# TR_i3_6A_Module_v5.net
KiCad netlist of a schematic drawn in EAGLE
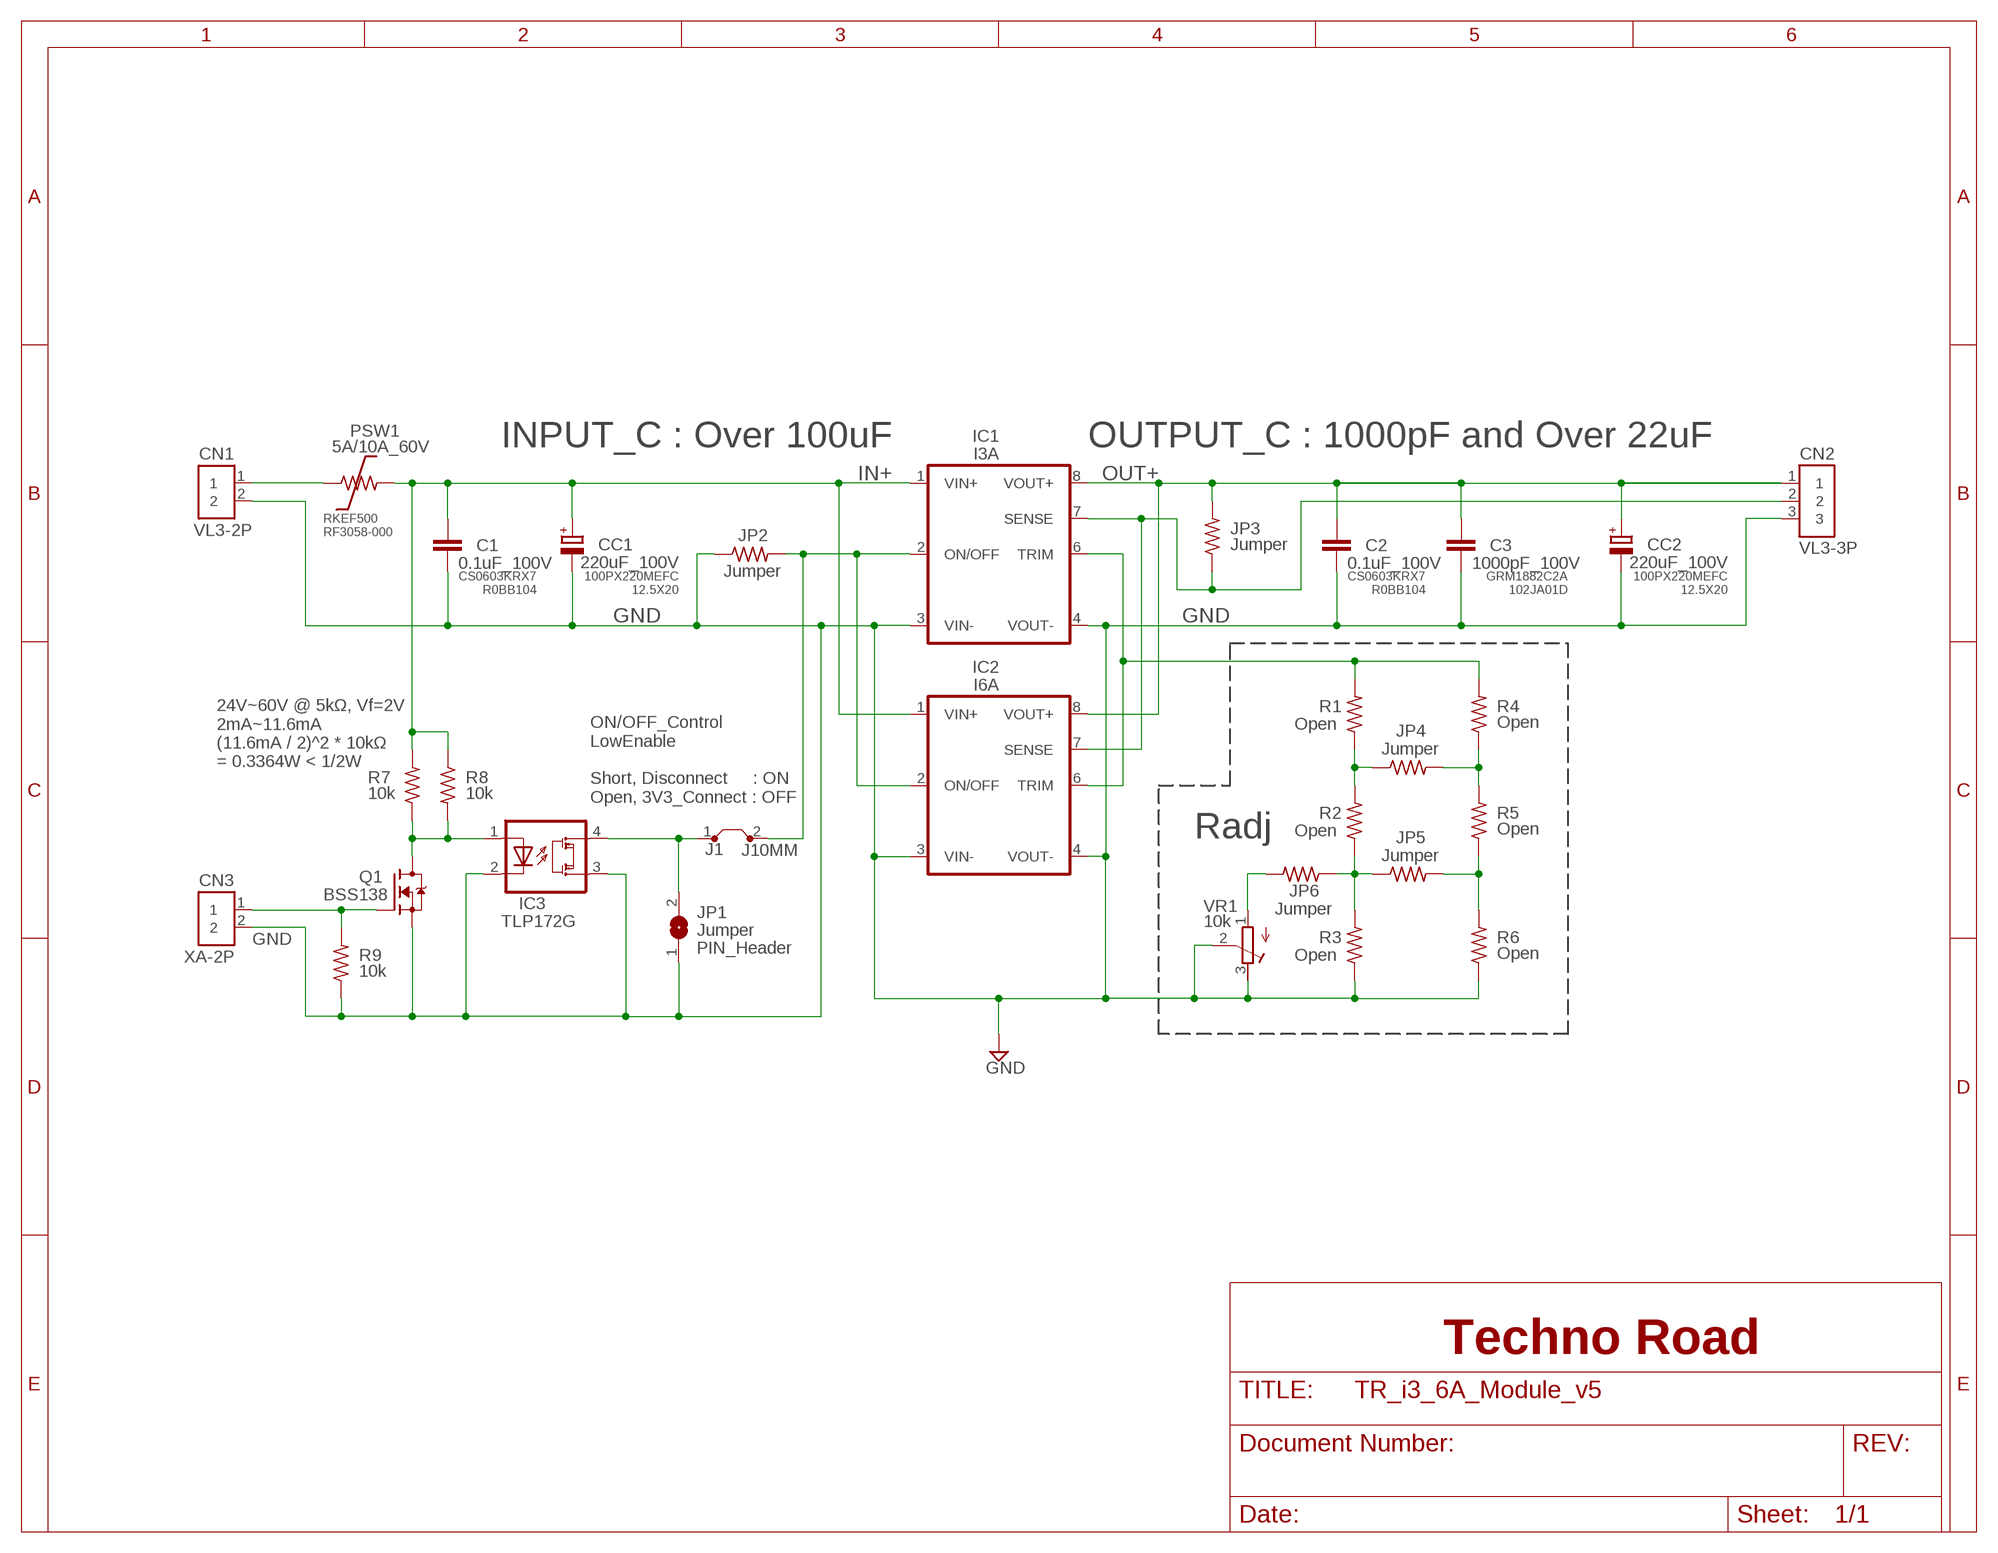
[diagram p0: schematic, sheet 1]

(export (version "E")
  (design (tool "Eeschema 10.0.6"))
  (components
    (comp (ref "C1")
      (value "0.1uF_100V")
      (footprint "eagle-import:C1608")
      (libsource (lib "eagle-import") (part "C1608"))
    )
    (comp (ref "C2")
      (value "0.1uF_100V")
      (footprint "eagle-import:C1608")
      (libsource (lib "eagle-import") (part "C1608"))
    )
    (comp (ref "C3")
      (value "1000pF_100V")
      (footprint "eagle-import:C1608")
      (libsource (lib "eagle-import") (part "C1608"))
    )
    (comp (ref "CC1")
      (value "220uF_100V")
      (footprint "eagle-import:CC0510")
      (libsource (lib "eagle-import") (part "CC0510"))
    )
    (comp (ref "CC2")
      (value "220uF_100V")
      (footprint "eagle-import:CC0510")
      (libsource (lib "eagle-import") (part "CC0510"))
    )
    (comp (ref "CN1")
      (value "VL3-2P")
      (footprint "eagle-import:VL3-2P")
      (libsource (lib "eagle-import") (part "2PVL3"))
    )
    (comp (ref "CN2")
      (value "VL3-3P")
      (footprint "eagle-import:VL3-3P")
      (libsource (lib "eagle-import") (part "3PVL3"))
    )
    (comp (ref "CN3")
      (value "XA-2P")
      (footprint "eagle-import:XA-2P_NH")
      (libsource (lib "eagle-import") (part "2PXA_NH"))
    )
    (comp (ref "IC1")
      (value "I3A")
      (footprint "eagle-import:I3A_SERIES")
      (libsource (lib "eagle-import") (part "I3A/I6A_SEREISI3A"))
    )
    (comp (ref "IC2")
      (value "I6A")
      (footprint "eagle-import:I6A_SERIES")
      (libsource (lib "eagle-import") (part "I3A/I6A_SEREISI6A"))
    )
    (comp (ref "IC3")
      (value "TLP172G")
      (footprint "eagle-import:11-5H1")
      (libsource (lib "eagle-import") (part "TLP172"))
    )
    (comp (ref "J1")
      (value "J10MM")
      (footprint "eagle-import:10")
      (libsource (lib "eagle-import") (part "J10MM"))
    )
    (comp (ref "JP1")
      (value "Jumper")
      (footprint "eagle-import:JP1D_HOLE")
      (libsource (lib "eagle-import") (part "JP1D"))
    )
    (comp (ref "JP2")
      (value "Jumper")
      (footprint "eagle-import:R1608_LARGE_PAD")
      (libsource (lib "eagle-import") (part "R1608_LARGE_PAD"))
    )
    (comp (ref "JP3")
      (value "Jumper")
      (footprint "eagle-import:R1608_LARGE_PAD")
      (libsource (lib "eagle-import") (part "R1608_LARGE_PAD"))
    )
    (comp (ref "JP4")
      (value "Jumper")
      (footprint "eagle-import:R1608_LARGE_PAD")
      (libsource (lib "eagle-import") (part "R1608_LARGE_PAD"))
    )
    (comp (ref "JP5")
      (value "Jumper")
      (footprint "eagle-import:R1608_LARGE_PAD")
      (libsource (lib "eagle-import") (part "R1608_LARGE_PAD"))
    )
    (comp (ref "JP6")
      (value "Jumper")
      (footprint "eagle-import:R1608_LARGE_PAD")
      (libsource (lib "eagle-import") (part "R1608_LARGE_PAD"))
    )
    (comp (ref "PSW1")
      (value "5A/10A_60V")
      (footprint "eagle-import:PSW-10.16MM_4MM")
      (libsource (lib "eagle-import") (part "PSW10.16MM_4MM"))
    )
    (comp (ref "Q1")
      (value "BSS138")
      (footprint "eagle-import:SOT-23-3")
      (libsource (lib "eagle-import") (part "BSS138"))
    )
    (comp (ref "R1")
      (value "Open")
      (footprint "eagle-import:R1608_LARGE_PAD")
      (libsource (lib "eagle-import") (part "R1608_LARGE_PAD"))
    )
    (comp (ref "R2")
      (value "Open")
      (footprint "eagle-import:R1608_LARGE_PAD")
      (libsource (lib "eagle-import") (part "R1608_LARGE_PAD"))
    )
    (comp (ref "R3")
      (value "Open")
      (footprint "eagle-import:R1608_LARGE_PAD")
      (libsource (lib "eagle-import") (part "R1608_LARGE_PAD"))
    )
    (comp (ref "R4")
      (value "Open")
      (footprint "eagle-import:R1608_LARGE_PAD")
      (libsource (lib "eagle-import") (part "R1608_LARGE_PAD"))
    )
    (comp (ref "R5")
      (value "Open")
      (footprint "eagle-import:R1608_LARGE_PAD")
      (libsource (lib "eagle-import") (part "R1608_LARGE_PAD"))
    )
    (comp (ref "R6")
      (value "Open")
      (footprint "eagle-import:R1608_LARGE_PAD")
      (libsource (lib "eagle-import") (part "R1608_LARGE_PAD"))
    )
    (comp (ref "R7")
      (value "10k")
      (footprint "eagle-import:0204V")
      (libsource (lib "eagle-import") (part "R-US_0204/2V"))
    )
    (comp (ref "R8")
      (value "10k")
      (footprint "eagle-import:0204V")
      (libsource (lib "eagle-import") (part "R-US_0204/2V"))
    )
    (comp (ref "R9")
      (value "10k")
      (footprint "eagle-import:R1608_LARGE_PAD")
      (libsource (lib "eagle-import") (part "R1608_LARGE_PAD"))
    )
    (comp (ref "VR1")
      (value "10k")
      (footprint "eagle-import:3361P")
      (libsource (lib "eagle-import") (part "R-TRIM3361P"))
    )
  )
  (nets
    (net (code "1") (name "/IN+") (class "Default")
      (node (ref "C1") (pin "1") (pinfunction "1_1") (pintype "passive"))
      (node (ref "CC1") (pin "+") (pinfunction "+_+") (pintype "passive"))
      (node (ref "IC1") (pin "1") (pinfunction "VIN+_1") (pintype "passive"))
      (node (ref "IC2") (pin "1") (pinfunction "VIN+_1") (pintype "passive"))
      (node (ref "PSW1") (pin "2") (pinfunction "2_2") (pintype "passive"))
      (node (ref "R7") (pin "2") (pinfunction "2_2") (pintype "passive"))
      (node (ref "R8") (pin "1") (pinfunction "1_1") (pintype "passive"))
    )
    (net (code "2") (name "/OUT+") (class "Default")
      (node (ref "C2") (pin "1") (pinfunction "1_1") (pintype "passive"))
      (node (ref "C3") (pin "1") (pinfunction "1_1") (pintype "passive"))
      (node (ref "CC2") (pin "+") (pinfunction "+_+") (pintype "passive"))
      (node (ref "CN2") (pin "1") (pinfunction "1_1") (pintype "passive"))
      (node (ref "IC1") (pin "8") (pinfunction "VOUT+_8") (pintype "passive"))
      (node (ref "IC2") (pin "8") (pinfunction "VOUT+_8") (pintype "passive"))
      (node (ref "JP3") (pin "2") (pinfunction "2_2") (pintype "passive"))
    )
    (net (code "3") (name "GND") (class "Default")
      (node (ref "C1") (pin "2") (pinfunction "2_2") (pintype "passive"))
      (node (ref "C2") (pin "2") (pinfunction "2_2") (pintype "passive"))
      (node (ref "C3") (pin "2") (pinfunction "2_2") (pintype "passive"))
      (node (ref "CC1") (pin "-") (pinfunction "-_-") (pintype "passive"))
      (node (ref "CC2") (pin "-") (pinfunction "-_-") (pintype "passive"))
      (node (ref "CN1") (pin "2") (pinfunction "2_2") (pintype "passive"))
      (node (ref "CN2") (pin "3") (pinfunction "3_3") (pintype "passive"))
      (node (ref "CN3") (pin "2") (pinfunction "2_2") (pintype "passive"))
      (node (ref "IC1") (pin "3") (pinfunction "VIN-_3") (pintype "passive"))
      (node (ref "IC1") (pin "4") (pinfunction "VOUT-_4") (pintype "passive"))
      (node (ref "IC2") (pin "3") (pinfunction "VIN-_3") (pintype "passive"))
      (node (ref "IC2") (pin "4") (pinfunction "VOUT-_4") (pintype "passive"))
      (node (ref "IC3") (pin "2") (pinfunction "C1_2") (pintype "passive"))
      (node (ref "IC3") (pin "3") (pinfunction "DRN1_3") (pintype "passive"))
      (node (ref "JP1") (pin "1") (pinfunction "1_1") (pintype "passive"))
      (node (ref "JP2") (pin "1") (pinfunction "1_1") (pintype "passive"))
      (node (ref "Q1") (pin "2") (pinfunction "S_2") (pintype "passive"))
      (node (ref "R3") (pin "1") (pinfunction "1_1") (pintype "passive"))
      (node (ref "R6") (pin "1") (pinfunction "1_1") (pintype "passive"))
      (node (ref "R9") (pin "1") (pinfunction "1_1") (pintype "passive"))
      (node (ref "VR1") (pin "2") (pinfunction "S_2") (pintype "passive"))
      (node (ref "VR1") (pin "3") (pinfunction "E_3") (pintype "passive"))
    )
    (net (code "4") (name "Net-(CN1-Pad1)") (class "Default")
      (node (ref "CN1") (pin "1") (pinfunction "1_1") (pintype "passive"))
      (node (ref "PSW1") (pin "1") (pinfunction "1_1") (pintype "passive"))
    )
    (net (code "5") (name "Net-(IC1-ON{slash}OFF)") (class "Default")
      (node (ref "IC1") (pin "2") (pinfunction "ON/OFF_2") (pintype "input"))
      (node (ref "IC2") (pin "2") (pinfunction "ON/OFF_2") (pintype "input"))
      (node (ref "J1") (pin "2") (pinfunction "2_2") (pintype "passive"))
      (node (ref "JP2") (pin "2") (pinfunction "2_2") (pintype "passive"))
    )
    (net (code "6") (name "Net-(IC1-SENSE)") (class "Default")
      (node (ref "CN2") (pin "2") (pinfunction "2_2") (pintype "passive"))
      (node (ref "IC1") (pin "7") (pinfunction "SENSE_7") (pintype "passive"))
      (node (ref "IC2") (pin "7") (pinfunction "SENSE_7") (pintype "passive"))
      (node (ref "JP3") (pin "1") (pinfunction "1_1") (pintype "passive"))
    )
    (net (code "7") (name "Net-(IC1-TRIM)") (class "Default")
      (node (ref "IC1") (pin "6") (pinfunction "TRIM_6") (pintype "input"))
      (node (ref "IC2") (pin "6") (pinfunction "TRIM_6") (pintype "input"))
      (node (ref "R1") (pin "2") (pinfunction "2_2") (pintype "passive"))
      (node (ref "R4") (pin "2") (pinfunction "2_2") (pintype "passive"))
    )
    (net (code "8") (name "Net-(IC3-A1)") (class "Default")
      (node (ref "IC3") (pin "1") (pinfunction "A1_1") (pintype "passive"))
      (node (ref "Q1") (pin "3") (pinfunction "D_3") (pintype "passive"))
      (node (ref "R7") (pin "1") (pinfunction "1_1") (pintype "passive"))
      (node (ref "R8") (pin "2") (pinfunction "2_2") (pintype "passive"))
    )
    (net (code "9") (name "Net-(IC3-DRN2)") (class "Default")
      (node (ref "IC3") (pin "4") (pinfunction "DRN2_4") (pintype "passive"))
      (node (ref "J1") (pin "1") (pinfunction "1_1") (pintype "passive"))
      (node (ref "JP1") (pin "2") (pinfunction "2_2") (pintype "passive"))
    )
    (net (code "10") (name "Net-(JP4-Pad1)") (class "Default")
      (node (ref "JP4") (pin "1") (pinfunction "1_1") (pintype "passive"))
      (node (ref "R1") (pin "1") (pinfunction "1_1") (pintype "passive"))
      (node (ref "R2") (pin "2") (pinfunction "2_2") (pintype "passive"))
    )
    (net (code "11") (name "Net-(JP4-Pad2)") (class "Default")
      (node (ref "JP4") (pin "2") (pinfunction "2_2") (pintype "passive"))
      (node (ref "R4") (pin "1") (pinfunction "1_1") (pintype "passive"))
      (node (ref "R5") (pin "2") (pinfunction "2_2") (pintype "passive"))
    )
    (net (code "12") (name "Net-(JP5-Pad1)") (class "Default")
      (node (ref "JP5") (pin "1") (pinfunction "1_1") (pintype "passive"))
      (node (ref "JP6") (pin "1") (pinfunction "1_1") (pintype "passive"))
      (node (ref "R2") (pin "1") (pinfunction "1_1") (pintype "passive"))
      (node (ref "R3") (pin "2") (pinfunction "2_2") (pintype "passive"))
    )
    (net (code "13") (name "Net-(JP5-Pad2)") (class "Default")
      (node (ref "JP5") (pin "2") (pinfunction "2_2") (pintype "passive"))
      (node (ref "R5") (pin "1") (pinfunction "1_1") (pintype "passive"))
      (node (ref "R6") (pin "2") (pinfunction "2_2") (pintype "passive"))
    )
    (net (code "14") (name "Net-(Q1-G)") (class "Default")
      (node (ref "CN3") (pin "1") (pinfunction "1_1") (pintype "passive"))
      (node (ref "Q1") (pin "1") (pinfunction "G_1") (pintype "passive"))
      (node (ref "R9") (pin "2") (pinfunction "2_2") (pintype "passive"))
    )
    (net (code "15") (name "Net-(VR1-A)") (class "Default")
      (node (ref "JP6") (pin "2") (pinfunction "2_2") (pintype "passive"))
      (node (ref "VR1") (pin "1") (pinfunction "A_1") (pintype "passive"))
    )
  )
)
